# 171-5782.net
KiCad netlist of a schematic drawn in Altium Designer
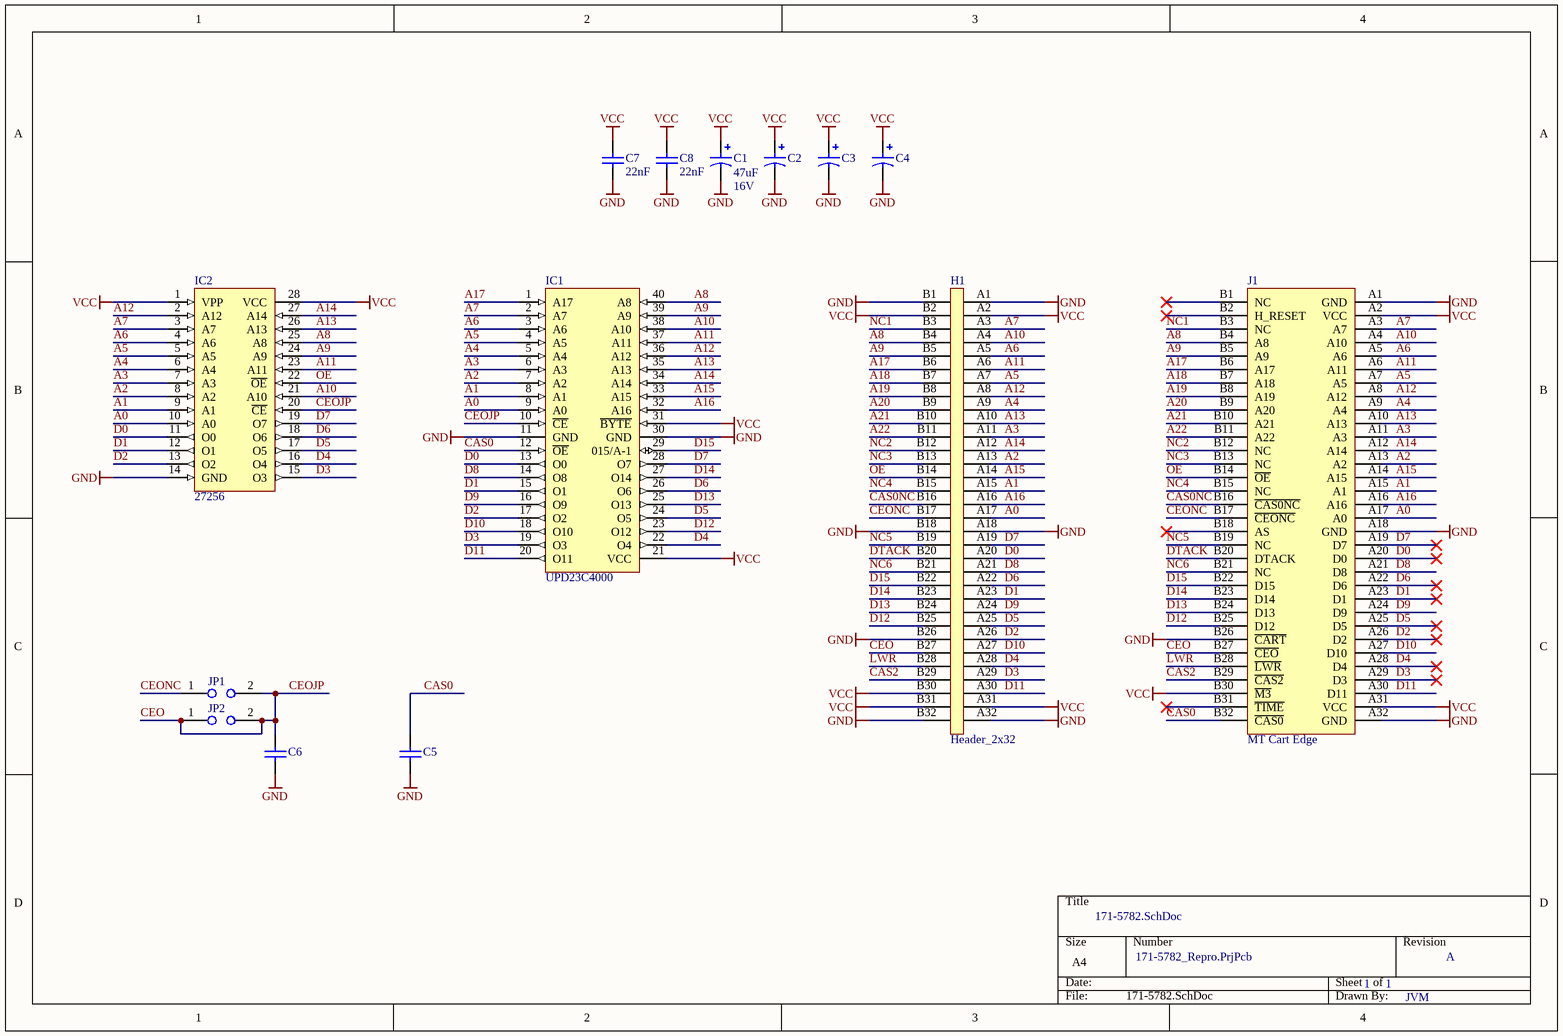
[diagram p0: 171-5782.SchDoc]

(export (version "E")
  (design (tool "Eeschema 10.0.6"))
  (components
    (comp (ref "C1")
      (value "47uF")
      (footprint "CapPol Mirror")
      (description "Polarized Capacitor, 2.54mm Pitch, 5mm Width, mirrored")
      (fields (field (name "VOLTAGE") "16V") (field (name "Comment") "Cap2.54P5.0D"))
      (libsource (lib "171-5782") (part "Cap2.54P5.0D_mirror"))
    )
    (comp (ref "C2")
      (value "Cap2.54P5.0D")
      (footprint "CapPol")
      (description "Polarized Capacitor, 2.54mm Pitch, 5mm Width")
      (libsource (lib "171-5782") (part "Cap2.54P5.0D"))
    )
    (comp (ref "C3")
      (value "Cap2.54P5.0D")
      (footprint "CapPol")
      (description "Polarized Capacitor, 2.54mm Pitch, 5mm Width")
      (libsource (lib "171-5782") (part "Cap2.54P5.0D"))
    )
    (comp (ref "C4")
      (value "Cap2.54P5.0D")
      (footprint "CapPol Mirror")
      (description "Polarized Capacitor, 2.54mm Pitch, 5mm Width, mirrored")
      (libsource (lib "171-5782") (part "Cap2.54P5.0D_mirror"))
    )
    (comp (ref "C5")
      (value "CapCer")
      (footprint "CapCer")
      (description "Capacitor (THT), Ceramic, 5.08mm Pitch")
      (libsource (lib "171-5782") (part "CapCer"))
    )
    (comp (ref "C6")
      (value "CapCer")
      (footprint "CapCer")
      (description "Capacitor (THT), Ceramic, 5.08mm Pitch")
      (libsource (lib "171-5782") (part "CapCer"))
    )
    (comp (ref "C7")
      (value "22nF")
      (footprint "CapCer")
      (description "Capacitor (THT), Ceramic, 5.08mm Pitch")
      (fields (field (name "Comment") "CapCer"))
      (libsource (lib "171-5782") (part "CapCer"))
    )
    (comp (ref "C8")
      (value "22nF")
      (footprint "CapCer")
      (description "Capacitor (THT), Ceramic, 5.08mm Pitch")
      (fields (field (name "Comment") "CapCer"))
      (libsource (lib "171-5782") (part "CapCer"))
    )
    (comp (ref "H1")
      (value "Header_2x32")
      (footprint "Header_2x32")
      (libsource (lib "171-5782") (part "Header_2x32"))
    )
    (comp (ref "IC1")
      (value "UPD23C4000")
      (footprint "UPD23C4000")
      (description "4M Mask Rom")
      (libsource (lib "171-5782") (part "UPD23C4000"))
    )
    (comp (ref "IC2")
      (value "27256")
      (footprint "27256")
      (description "256K EPROM")
      (libsource (lib "171-5782") (part "27256"))
    )
    (comp (ref "J1")
      (value "MT Cart Edge")
      (footprint "MT_Cart_Edge")
      (libsource (lib "171-5782") (part "MT_CART_EDGE_CON"))
    )
    (comp (ref "JP1")
      (value "SolderBridge")
      (footprint "SOLDER_BRIDGE")
      (description "Solder Bridge")
      (libsource (lib "171-5782") (part "SolderBridge"))
    )
    (comp (ref "JP2")
      (value "SolderBridge")
      (footprint "SOLDER_BRIDGE")
      (description "Solder Bridge")
      (libsource (lib "171-5782") (part "SolderBridge"))
    )
  )
  (nets
    (net (code "1") (name "/A0") (class "Default")
      (node (ref "H1") (pin "A17") (pintype "passive"))
      (node (ref "IC1") (pin "9") (pinfunction "A0_9") (pintype "input"))
      (node (ref "IC2") (pin "10") (pinfunction "A0_10") (pintype "input"))
      (node (ref "J1") (pin "A17") (pinfunction "A0_A17") (pintype "passive"))
    )
    (net (code "2") (name "/A1") (class "Default")
      (node (ref "H1") (pin "A15") (pintype "passive"))
      (node (ref "IC1") (pin "8") (pinfunction "A1_8") (pintype "input"))
      (node (ref "IC2") (pin "9") (pinfunction "A1_9") (pintype "input"))
      (node (ref "J1") (pin "A15") (pinfunction "A1_A15") (pintype "passive"))
    )
    (net (code "3") (name "/A2") (class "Default")
      (node (ref "H1") (pin "A13") (pintype "passive"))
      (node (ref "IC1") (pin "7") (pinfunction "A2_7") (pintype "input"))
      (node (ref "IC2") (pin "8") (pinfunction "A2_8") (pintype "input"))
      (node (ref "J1") (pin "A13") (pinfunction "A2_A13") (pintype "passive"))
    )
    (net (code "4") (name "/A3") (class "Default")
      (node (ref "H1") (pin "A11") (pintype "passive"))
      (node (ref "IC1") (pin "6") (pinfunction "A3_6") (pintype "input"))
      (node (ref "IC2") (pin "7") (pinfunction "A3_7") (pintype "input"))
      (node (ref "J1") (pin "A11") (pinfunction "A3_A11") (pintype "passive"))
    )
    (net (code "5") (name "/A4") (class "Default")
      (node (ref "H1") (pin "A9") (pintype "passive"))
      (node (ref "IC1") (pin "5") (pinfunction "A4_5") (pintype "input"))
      (node (ref "IC2") (pin "6") (pinfunction "A4_6") (pintype "input"))
      (node (ref "J1") (pin "A9") (pinfunction "A4_A9") (pintype "passive"))
    )
    (net (code "6") (name "/A5") (class "Default")
      (node (ref "H1") (pin "A7") (pintype "passive"))
      (node (ref "IC1") (pin "4") (pinfunction "A5_4") (pintype "input"))
      (node (ref "IC2") (pin "5") (pinfunction "A5_5") (pintype "input"))
      (node (ref "J1") (pin "A7") (pinfunction "A5_A7") (pintype "passive"))
    )
    (net (code "7") (name "/A6") (class "Default")
      (node (ref "H1") (pin "A5") (pintype "passive"))
      (node (ref "IC1") (pin "3") (pinfunction "A6_3") (pintype "input"))
      (node (ref "IC2") (pin "4") (pinfunction "A6_4") (pintype "input"))
      (node (ref "J1") (pin "A5") (pinfunction "A6_A5") (pintype "passive"))
    )
    (net (code "8") (name "/A7") (class "Default")
      (node (ref "H1") (pin "A3") (pintype "passive"))
      (node (ref "IC1") (pin "2") (pinfunction "A7_2") (pintype "input"))
      (node (ref "IC2") (pin "3") (pinfunction "A7_3") (pintype "input"))
      (node (ref "J1") (pin "A3") (pinfunction "A7_A3") (pintype "passive"))
    )
    (net (code "9") (name "/A8") (class "Default")
      (node (ref "H1") (pin "B4") (pintype "passive"))
      (node (ref "IC1") (pin "40") (pinfunction "A8_40") (pintype "input"))
      (node (ref "IC2") (pin "25") (pinfunction "A8_25") (pintype "input"))
      (node (ref "J1") (pin "B4") (pinfunction "A8_B4") (pintype "passive"))
    )
    (net (code "10") (name "/A9") (class "Default")
      (node (ref "H1") (pin "B5") (pintype "passive"))
      (node (ref "IC1") (pin "39") (pinfunction "A9_39") (pintype "input"))
      (node (ref "IC2") (pin "24") (pinfunction "A9_24") (pintype "input"))
      (node (ref "J1") (pin "B5") (pinfunction "A9_B5") (pintype "passive"))
    )
    (net (code "11") (name "/A10") (class "Default")
      (node (ref "H1") (pin "A4") (pintype "passive"))
      (node (ref "IC1") (pin "38") (pinfunction "A10_38") (pintype "input"))
      (node (ref "IC2") (pin "21") (pinfunction "A10_21") (pintype "input"))
      (node (ref "J1") (pin "A4") (pinfunction "A10_A4") (pintype "passive"))
    )
    (net (code "12") (name "/A11") (class "Default")
      (node (ref "H1") (pin "A6") (pintype "passive"))
      (node (ref "IC1") (pin "37") (pinfunction "A11_37") (pintype "input"))
      (node (ref "IC2") (pin "23") (pinfunction "A11_23") (pintype "input"))
      (node (ref "J1") (pin "A6") (pinfunction "A11_A6") (pintype "passive"))
    )
    (net (code "13") (name "/A12") (class "Default")
      (node (ref "H1") (pin "A8") (pintype "passive"))
      (node (ref "IC1") (pin "36") (pinfunction "A12_36") (pintype "input"))
      (node (ref "IC2") (pin "2") (pinfunction "A12_2") (pintype "input"))
      (node (ref "J1") (pin "A8") (pinfunction "A12_A8") (pintype "passive"))
    )
    (net (code "14") (name "/A13") (class "Default")
      (node (ref "H1") (pin "A10") (pintype "passive"))
      (node (ref "IC1") (pin "35") (pinfunction "A13_35") (pintype "input"))
      (node (ref "IC2") (pin "26") (pinfunction "A13_26") (pintype "input"))
      (node (ref "J1") (pin "A10") (pinfunction "A13_A10") (pintype "passive"))
    )
    (net (code "15") (name "/A14") (class "Default")
      (node (ref "H1") (pin "A12") (pintype "passive"))
      (node (ref "IC1") (pin "34") (pinfunction "A14_34") (pintype "input"))
      (node (ref "IC2") (pin "27") (pinfunction "A14_27") (pintype "input"))
      (node (ref "J1") (pin "A12") (pinfunction "A14_A12") (pintype "passive"))
    )
    (net (code "16") (name "/A15") (class "Default")
      (node (ref "H1") (pin "A14") (pintype "passive"))
      (node (ref "IC1") (pin "33") (pinfunction "A15_33") (pintype "input"))
      (node (ref "J1") (pin "A14") (pinfunction "A15_A14") (pintype "passive"))
    )
    (net (code "17") (name "/A16") (class "Default")
      (node (ref "H1") (pin "A16") (pintype "passive"))
      (node (ref "IC1") (pin "32") (pinfunction "A16_32") (pintype "input"))
      (node (ref "J1") (pin "A16") (pinfunction "A16_A16") (pintype "passive"))
    )
    (net (code "18") (name "/A17") (class "Default")
      (node (ref "H1") (pin "B6") (pintype "passive"))
      (node (ref "IC1") (pin "1") (pinfunction "A17_1") (pintype "input"))
      (node (ref "J1") (pin "B6") (pinfunction "A17_B6") (pintype "passive"))
    )
    (net (code "19") (name "/A18") (class "Default")
      (node (ref "H1") (pin "B7") (pintype "passive"))
      (node (ref "J1") (pin "B7") (pinfunction "A18_B7") (pintype "passive"))
    )
    (net (code "20") (name "/A19") (class "Default")
      (node (ref "H1") (pin "B8") (pintype "passive"))
      (node (ref "J1") (pin "B8") (pinfunction "A19_B8") (pintype "passive"))
    )
    (net (code "21") (name "/A20") (class "Default")
      (node (ref "H1") (pin "B9") (pintype "passive"))
      (node (ref "J1") (pin "B9") (pinfunction "A20_B9") (pintype "passive"))
    )
    (net (code "22") (name "/A21") (class "Default")
      (node (ref "H1") (pin "B10") (pintype "passive"))
      (node (ref "J1") (pin "B10") (pinfunction "A21_B10") (pintype "passive"))
    )
    (net (code "23") (name "/A22") (class "Default")
      (node (ref "H1") (pin "B11") (pintype "passive"))
      (node (ref "J1") (pin "B11") (pinfunction "A22_B11") (pintype "passive"))
    )
    (net (code "24") (name "/CAS0") (class "Default")
      (node (ref "C5") (pin "2") (pinfunction "2_2") (pintype "passive"))
      (node (ref "IC1") (pin "12") (pinfunction "~{OE}_12") (pintype "input"))
      (node (ref "J1") (pin "B32") (pinfunction "~{CAS0}_B32") (pintype "passive"))
    )
    (net (code "25") (name "/CAS0NC") (class "Default")
      (node (ref "H1") (pin "B16") (pintype "passive"))
      (node (ref "J1") (pin "B16") (pinfunction "~{CAS0NC}_B16") (pintype "passive"))
    )
    (net (code "26") (name "/CAS2") (class "Default")
      (node (ref "H1") (pin "B29") (pintype "passive"))
      (node (ref "J1") (pin "B29") (pinfunction "~{CAS2}_B29") (pintype "passive"))
    )
    (net (code "27") (name "/CEO") (class "Default")
      (node (ref "C6") (pin "2") (pinfunction "2_2") (pintype "passive"))
      (node (ref "H1") (pin "B27") (pintype "passive"))
      (node (ref "IC1") (pin "10") (pinfunction "~{CE}_10") (pintype "input"))
      (node (ref "IC2") (pin "20") (pinfunction "~{CE}_20") (pintype "input"))
      (node (ref "J1") (pin "B27") (pinfunction "~{CEO}_B27") (pintype "passive"))
      (node (ref "JP1") (pin "2") (pinfunction "2_2") (pintype "passive"))
      (node (ref "JP2") (pin "1") (pinfunction "1_1") (pintype "passive"))
      (node (ref "JP2") (pin "2") (pinfunction "2_2") (pintype "passive"))
    )
    (net (code "28") (name "/CEONC") (class "Default")
      (node (ref "H1") (pin "B17") (pintype "passive"))
      (node (ref "J1") (pin "B17") (pinfunction "~{CEONC}_B17") (pintype "passive"))
      (node (ref "JP1") (pin "1") (pinfunction "1_1") (pintype "passive"))
    )
    (net (code "29") (name "/D0") (class "Default")
      (node (ref "H1") (pin "A20") (pintype "passive"))
      (node (ref "IC1") (pin "13") (pinfunction "O0_13") (pintype "output"))
      (node (ref "IC2") (pin "11") (pinfunction "O0_11") (pintype "output"))
      (node (ref "J1") (pin "A20") (pinfunction "D0_A20") (pintype "passive"))
    )
    (net (code "30") (name "/D1") (class "Default")
      (node (ref "H1") (pin "A23") (pintype "passive"))
      (node (ref "IC1") (pin "15") (pinfunction "O1_15") (pintype "output"))
      (node (ref "IC2") (pin "12") (pinfunction "O1_12") (pintype "output"))
      (node (ref "J1") (pin "A23") (pinfunction "D1_A23") (pintype "passive"))
    )
    (net (code "31") (name "/D2") (class "Default")
      (node (ref "H1") (pin "A26") (pintype "passive"))
      (node (ref "IC1") (pin "17") (pinfunction "O2_17") (pintype "output"))
      (node (ref "IC2") (pin "13") (pinfunction "O2_13") (pintype "output"))
      (node (ref "J1") (pin "A26") (pinfunction "D2_A26") (pintype "passive"))
    )
    (net (code "32") (name "/D3") (class "Default")
      (node (ref "H1") (pin "A29") (pintype "passive"))
      (node (ref "IC1") (pin "19") (pinfunction "O3_19") (pintype "output"))
      (node (ref "IC2") (pin "15") (pinfunction "O3_15") (pintype "output"))
      (node (ref "J1") (pin "A29") (pinfunction "D3_A29") (pintype "passive"))
    )
    (net (code "33") (name "/D4") (class "Default")
      (node (ref "H1") (pin "A28") (pintype "passive"))
      (node (ref "IC1") (pin "22") (pinfunction "O4_22") (pintype "output"))
      (node (ref "IC2") (pin "16") (pinfunction "O4_16") (pintype "output"))
      (node (ref "J1") (pin "A28") (pinfunction "D4_A28") (pintype "passive"))
    )
    (net (code "34") (name "/D5") (class "Default")
      (node (ref "H1") (pin "A25") (pintype "passive"))
      (node (ref "IC1") (pin "24") (pinfunction "O5_24") (pintype "output"))
      (node (ref "IC2") (pin "17") (pinfunction "O5_17") (pintype "output"))
      (node (ref "J1") (pin "A25") (pinfunction "D5_A25") (pintype "passive"))
    )
    (net (code "35") (name "/D6") (class "Default")
      (node (ref "H1") (pin "A22") (pintype "passive"))
      (node (ref "IC1") (pin "26") (pinfunction "O6_26") (pintype "output"))
      (node (ref "IC2") (pin "18") (pinfunction "O6_18") (pintype "output"))
      (node (ref "J1") (pin "A22") (pinfunction "D6_A22") (pintype "passive"))
    )
    (net (code "36") (name "/D7") (class "Default")
      (node (ref "H1") (pin "A19") (pintype "passive"))
      (node (ref "IC1") (pin "28") (pinfunction "O7_28") (pintype "output"))
      (node (ref "IC2") (pin "19") (pinfunction "O7_19") (pintype "output"))
      (node (ref "J1") (pin "A19") (pinfunction "D7_A19") (pintype "passive"))
    )
    (net (code "37") (name "/D8") (class "Default")
      (node (ref "H1") (pin "A21") (pintype "passive"))
      (node (ref "IC1") (pin "14") (pinfunction "O8_14") (pintype "output"))
      (node (ref "J1") (pin "A21") (pinfunction "D8_A21") (pintype "passive"))
    )
    (net (code "38") (name "/D9") (class "Default")
      (node (ref "H1") (pin "A24") (pintype "passive"))
      (node (ref "IC1") (pin "16") (pinfunction "O9_16") (pintype "output"))
      (node (ref "J1") (pin "A24") (pinfunction "D9_A24") (pintype "passive"))
    )
    (net (code "39") (name "/D10") (class "Default")
      (node (ref "H1") (pin "A27") (pintype "passive"))
      (node (ref "IC1") (pin "18") (pinfunction "O10_18") (pintype "output"))
      (node (ref "J1") (pin "A27") (pinfunction "D10_A27") (pintype "passive"))
    )
    (net (code "40") (name "/D11") (class "Default")
      (node (ref "H1") (pin "A30") (pintype "passive"))
      (node (ref "IC1") (pin "20") (pinfunction "O11_20") (pintype "output"))
      (node (ref "J1") (pin "A30") (pinfunction "D11_A30") (pintype "passive"))
    )
    (net (code "41") (name "/D12") (class "Default")
      (node (ref "H1") (pin "B25") (pintype "passive"))
      (node (ref "IC1") (pin "23") (pinfunction "O12_23") (pintype "output"))
      (node (ref "J1") (pin "B25") (pinfunction "D12_B25") (pintype "passive"))
    )
    (net (code "42") (name "/D13") (class "Default")
      (node (ref "H1") (pin "B24") (pintype "passive"))
      (node (ref "IC1") (pin "25") (pinfunction "O13_25") (pintype "output"))
      (node (ref "J1") (pin "B24") (pinfunction "D13_B24") (pintype "passive"))
    )
    (net (code "43") (name "/D14") (class "Default")
      (node (ref "H1") (pin "B23") (pintype "passive"))
      (node (ref "IC1") (pin "27") (pinfunction "O14_27") (pintype "output"))
      (node (ref "J1") (pin "B23") (pinfunction "D14_B23") (pintype "passive"))
    )
    (net (code "44") (name "/D15") (class "Default")
      (node (ref "H1") (pin "B22") (pintype "passive"))
      (node (ref "IC1") (pin "29") (pinfunction "015/A-1_29") (pintype "bidirectional"))
      (node (ref "J1") (pin "B22") (pinfunction "D15_B22") (pintype "passive"))
    )
    (net (code "45") (name "/DTACK") (class "Default")
      (node (ref "H1") (pin "B20") (pintype "passive"))
      (node (ref "J1") (pin "B20") (pinfunction "DTACK_B20") (pintype "passive"))
    )
    (net (code "46") (name "/LWR") (class "Default")
      (node (ref "H1") (pin "B28") (pintype "passive"))
      (node (ref "J1") (pin "B28") (pinfunction "~{LWR}_B28") (pintype "passive"))
    )
    (net (code "47") (name "/NC1") (class "Default")
      (node (ref "H1") (pin "B3") (pintype "passive"))
      (node (ref "J1") (pin "B3") (pinfunction "NC_B3") (pintype "passive"))
    )
    (net (code "48") (name "/NC2") (class "Default")
      (node (ref "H1") (pin "B12") (pintype "passive"))
      (node (ref "J1") (pin "B12") (pinfunction "NC_B12") (pintype "passive"))
    )
    (net (code "49") (name "/NC3") (class "Default")
      (node (ref "H1") (pin "B13") (pintype "passive"))
      (node (ref "J1") (pin "B13") (pinfunction "NC_B13") (pintype "passive"))
    )
    (net (code "50") (name "/NC4") (class "Default")
      (node (ref "H1") (pin "B15") (pintype "passive"))
      (node (ref "J1") (pin "B15") (pinfunction "NC_B15") (pintype "passive"))
    )
    (net (code "51") (name "/NC5") (class "Default")
      (node (ref "H1") (pin "B19") (pintype "passive"))
      (node (ref "J1") (pin "B19") (pinfunction "NC_B19") (pintype "passive"))
    )
    (net (code "52") (name "/NC6") (class "Default")
      (node (ref "H1") (pin "B21") (pintype "passive"))
      (node (ref "J1") (pin "B21") (pinfunction "NC_B21") (pintype "passive"))
    )
    (net (code "53") (name "/OE") (class "Default")
      (node (ref "H1") (pin "B14") (pintype "passive"))
      (node (ref "IC2") (pin "22") (pinfunction "~{OE}_22") (pintype "input"))
      (node (ref "J1") (pin "B14") (pinfunction "~{OE}_B14") (pintype "passive"))
    )
    (net (code "54") (name "GND") (class "Default")
      (node (ref "C1") (pin "2") (pinfunction "2_2") (pintype "passive"))
      (node (ref "C2") (pin "2") (pinfunction "2_2") (pintype "passive"))
      (node (ref "C3") (pin "2") (pinfunction "2_2") (pintype "passive"))
      (node (ref "C4") (pin "2") (pinfunction "2_2") (pintype "passive"))
      (node (ref "C5") (pin "1") (pinfunction "1_1") (pintype "passive"))
      (node (ref "C6") (pin "1") (pinfunction "1_1") (pintype "passive"))
      (node (ref "C7") (pin "1") (pinfunction "1_1") (pintype "passive"))
      (node (ref "C8") (pin "1") (pinfunction "1_1") (pintype "passive"))
      (node (ref "H1") (pin "A1") (pintype "passive"))
      (node (ref "H1") (pin "A18") (pintype "passive"))
      (node (ref "H1") (pin "A32") (pintype "passive"))
      (node (ref "H1") (pin "B1") (pintype "passive"))
      (node (ref "H1") (pin "B18") (pintype "passive"))
      (node (ref "H1") (pin "B26") (pintype "passive"))
      (node (ref "H1") (pin "B32") (pintype "passive"))
      (node (ref "IC1") (pin "11") (pinfunction "GND_11") (pintype "power_in"))
      (node (ref "IC1") (pin "30") (pinfunction "GND_30") (pintype "power_in"))
      (node (ref "IC2") (pin "14") (pinfunction "GND_14") (pintype "input"))
      (node (ref "J1") (pin "A1") (pinfunction "GND_A1") (pintype "passive"))
      (node (ref "J1") (pin "A18") (pinfunction "GND_A18") (pintype "passive"))
      (node (ref "J1") (pin "A32") (pinfunction "GND_A32") (pintype "passive"))
      (node (ref "J1") (pin "B26") (pinfunction "~{CART}_B26") (pintype "passive"))
    )
    (net (code "55") (name "VCC") (class "Default")
      (node (ref "C1") (pin "1") (pinfunction "1_1") (pintype "passive"))
      (node (ref "C2") (pin "1") (pinfunction "1_1") (pintype "passive"))
      (node (ref "C3") (pin "1") (pinfunction "1_1") (pintype "passive"))
      (node (ref "C4") (pin "1") (pinfunction "1_1") (pintype "passive"))
      (node (ref "C7") (pin "2") (pinfunction "2_2") (pintype "passive"))
      (node (ref "C8") (pin "2") (pinfunction "2_2") (pintype "passive"))
      (node (ref "H1") (pin "A2") (pintype "passive"))
      (node (ref "H1") (pin "A31") (pintype "passive"))
      (node (ref "H1") (pin "B2") (pintype "passive"))
      (node (ref "H1") (pin "B30") (pintype "passive"))
      (node (ref "H1") (pin "B31") (pintype "passive"))
      (node (ref "IC1") (pin "21") (pinfunction "VCC_21") (pintype "power_in"))
      (node (ref "IC1") (pin "31") (pinfunction "~{BYTE}_31") (pintype "input"))
      (node (ref "IC2") (pin "1") (pinfunction "VPP_1") (pintype "input"))
      (node (ref "IC2") (pin "28") (pinfunction "VCC_28") (pintype "power_in"))
      (node (ref "J1") (pin "A2") (pinfunction "VCC_A2") (pintype "passive"))
      (node (ref "J1") (pin "A31") (pinfunction "VCC_A31") (pintype "passive"))
      (node (ref "J1") (pin "B30") (pinfunction "~{M3}_B30") (pintype "passive"))
    )
    (net (code "56") (name "unconnected-(J1-AS-PadB18)") (class "Default")
      (node (ref "J1") (pin "B18") (pinfunction "AS_B18") (pintype "passive+no_connect"))
    )
    (net (code "57") (name "unconnected-(J1-H_RESET-PadB2)") (class "Default")
      (node (ref "J1") (pin "B2") (pinfunction "H_RESET_B2") (pintype "passive+no_connect"))
    )
    (net (code "58") (name "unconnected-(J1-NC-PadB1)") (class "Default")
      (node (ref "J1") (pin "B1") (pinfunction "NC_B1") (pintype "passive+no_connect"))
    )
    (net (code "59") (name "unconnected-(J1-~{TIME}-PadB31)") (class "Default")
      (node (ref "J1") (pin "B31") (pinfunction "~{TIME}_B31") (pintype "passive+no_connect"))
    )
  )
)
